# Sensor.net
KiCad netlist of a schematic drawn in Altium Designer
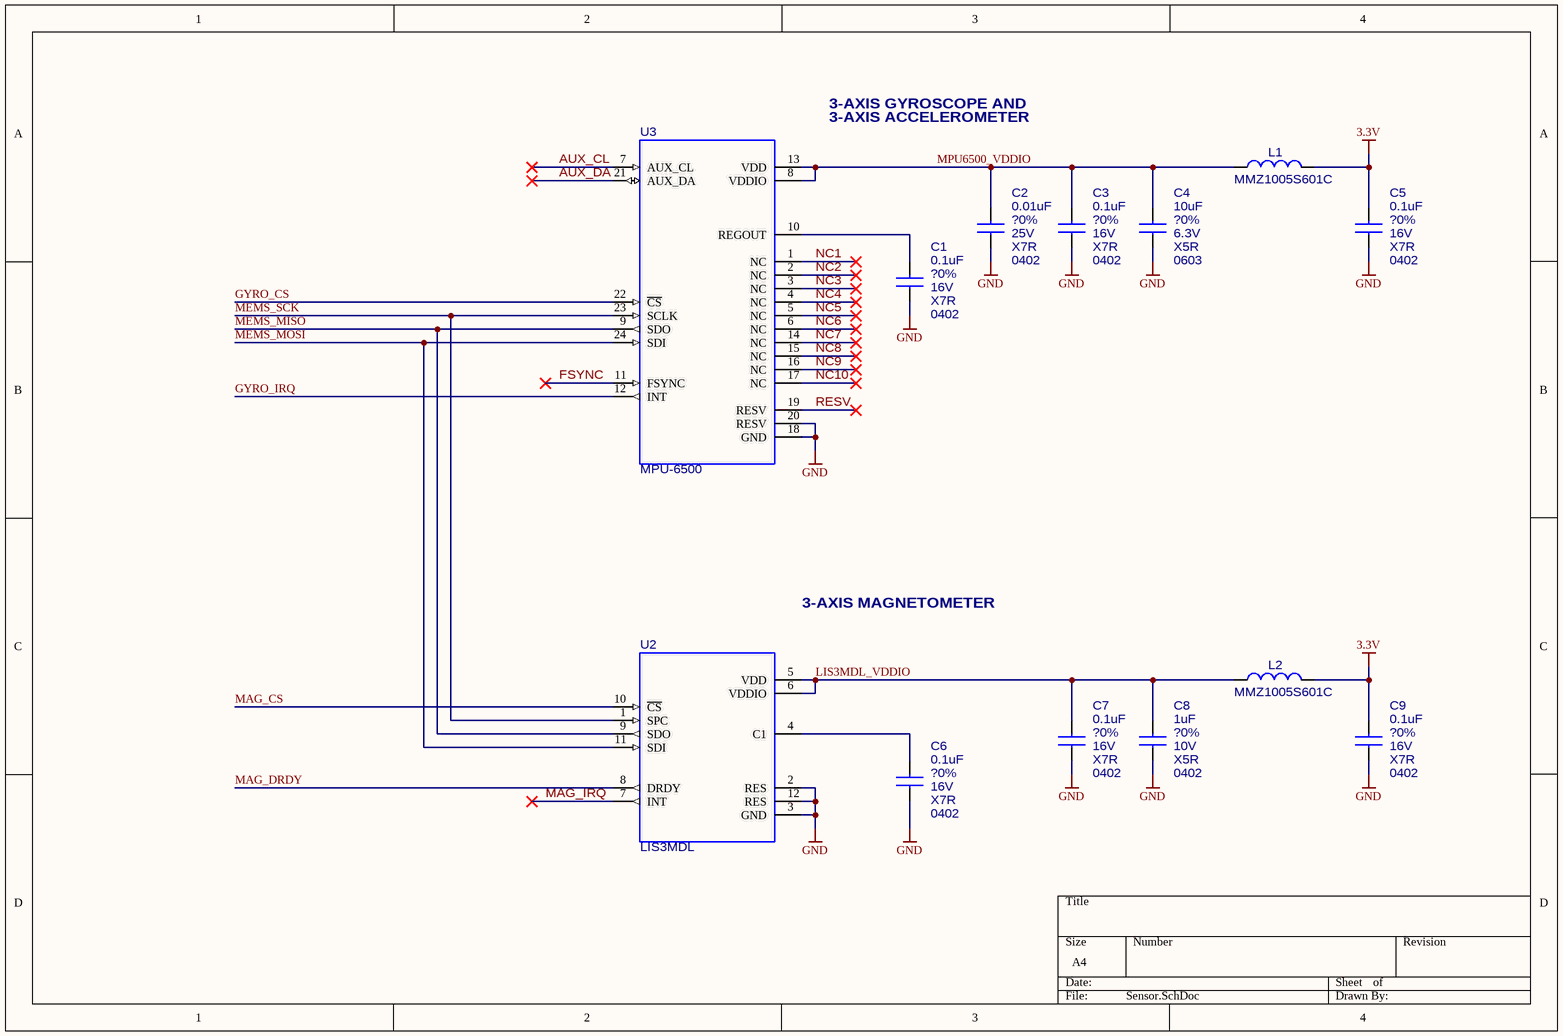
[diagram p0: Sensor.SchDoc]

(export (version "E")
  (design (tool "Eeschema 10.0.6"))
  (components
    (comp (ref "C1")
      (value "0.1uF")
      (footprint "CAP_CERAMIC_0402")
      (description "CAP, CERAMIC, 0.1uF, ?0%, 16V, X7R, 0402")
      (fields
        (field (name "MANUFACTURER") "MURATA ELECTRONICS")
        (field (name "PART NUMBER") "GRM155R71C104KA88D")
        (field (name "TOLERANCE") "?0%")
        (field (name "VOLTAGE") "16V")
        (field (name "DIELECTRIC") "X7R")
        (field (name "PACKAGE") "0402")
      )
      (libsource (lib "DK2") (part "CAP, CERAMIC"))
    )
    (comp (ref "C2")
      (value "0.01uF")
      (footprint "CAP_CERAMIC_0402")
      (description "CAP, CERAMIC, 0.01uF, ?0%, 25V, X7R, 0402")
      (fields
        (field (name "MANUFACTURER") "MURATA ELECTRONICS")
        (field (name "PART NUMBER") "GRM155R71E103KA01D")
        (field (name "TOLERANCE") "?0%")
        (field (name "VOLTAGE") "25V")
        (field (name "DIELECTRIC") "X7R")
        (field (name "PACKAGE") "0402")
      )
      (libsource (lib "DK2") (part "CAP, CERAMIC"))
    )
    (comp (ref "C3")
      (value "0.1uF")
      (footprint "CAP_CERAMIC_0402")
      (description "CAP, CERAMIC, 0.1uF, ?0%, 16V, X7R, 0402")
      (fields
        (field (name "MANUFACTURER") "MURATA ELECTRONICS")
        (field (name "PART NUMBER") "GRM155R71C104KA88D")
        (field (name "TOLERANCE") "?0%")
        (field (name "VOLTAGE") "16V")
        (field (name "DIELECTRIC") "X7R")
        (field (name "PACKAGE") "0402")
      )
      (libsource (lib "DK2") (part "CAP, CERAMIC"))
    )
    (comp (ref "C4")
      (value "10uF")
      (footprint "CAP_CERAMIC_0603")
      (description "CAP, CERAMIC, 10uF, ?0%, 6.3V, X5R, 0603")
      (fields
        (field (name "MANUFACTURER") "MURATA ELECTRONICS")
        (field (name "PART NUMBER") "GRM188R60J106ME47D")
        (field (name "TOLERANCE") "?0%")
        (field (name "VOLTAGE") "6.3V")
        (field (name "DIELECTRIC") "X5R")
        (field (name "PACKAGE") "0603")
      )
      (libsource (lib "DK2") (part "CAP, CERAMIC"))
    )
    (comp (ref "C5")
      (value "0.1uF")
      (footprint "CAP_CERAMIC_0402")
      (description "CAP, CERAMIC, 0.1uF, ?0%, 16V, X7R, 0402")
      (fields
        (field (name "MANUFACTURER") "MURATA ELECTRONICS")
        (field (name "PART NUMBER") "GRM155R71C104KA88D")
        (field (name "TOLERANCE") "?0%")
        (field (name "VOLTAGE") "16V")
        (field (name "DIELECTRIC") "X7R")
        (field (name "PACKAGE") "0402")
      )
      (libsource (lib "DK2") (part "CAP, CERAMIC"))
    )
    (comp (ref "C6")
      (value "0.1uF")
      (footprint "CAP_CERAMIC_0402")
      (description "CAP, CERAMIC, 0.1uF, ?0%, 16V, X7R, 0402")
      (fields
        (field (name "MANUFACTURER") "MURATA ELECTRONICS")
        (field (name "PART NUMBER") "GRM155R71C104KA88D")
        (field (name "TOLERANCE") "?0%")
        (field (name "VOLTAGE") "16V")
        (field (name "DIELECTRIC") "X7R")
        (field (name "PACKAGE") "0402")
      )
      (libsource (lib "DK2") (part "CAP, CERAMIC"))
    )
    (comp (ref "C7")
      (value "0.1uF")
      (footprint "CAP_CERAMIC_0402")
      (description "CAP, CERAMIC, 0.1uF, ?0%, 16V, X7R, 0402")
      (fields
        (field (name "MANUFACTURER") "MURATA ELECTRONICS")
        (field (name "PART NUMBER") "GRM155R71C104KA88D")
        (field (name "TOLERANCE") "?0%")
        (field (name "VOLTAGE") "16V")
        (field (name "DIELECTRIC") "X7R")
        (field (name "PACKAGE") "0402")
      )
      (libsource (lib "DK2") (part "CAP, CERAMIC"))
    )
    (comp (ref "C8")
      (value "1uF")
      (footprint "CAP_CERAMIC_0402")
      (description "CAP, CERAMIC, 1uF, ?0%, 10V, X5R, 0402")
      (fields
        (field (name "MANUFACTURER") "MURATA ELECTRONICS")
        (field (name "PART NUMBER") "GRM155R61A105KE15D")
        (field (name "TOLERANCE") "?0%")
        (field (name "VOLTAGE") "10V")
        (field (name "DIELECTRIC") "X5R")
        (field (name "PACKAGE") "0402")
      )
      (libsource (lib "DK2") (part "CAP, CERAMIC"))
    )
    (comp (ref "C9")
      (value "0.1uF")
      (footprint "CAP_CERAMIC_0402")
      (description "CAP, CERAMIC, 0.1uF, ?0%, 16V, X7R, 0402")
      (fields
        (field (name "MANUFACTURER") "MURATA ELECTRONICS")
        (field (name "PART NUMBER") "GRM155R71C104KA88D")
        (field (name "TOLERANCE") "?0%")
        (field (name "VOLTAGE") "16V")
        (field (name "DIELECTRIC") "X7R")
        (field (name "PACKAGE") "0402")
      )
      (libsource (lib "DK2") (part "CAP, CERAMIC"))
    )
    (comp (ref "L1")
      (value "MMZ1005S601C")
      (footprint "INDUCTOR_0402")
      (description "FERRITE CHIP BEAD, 600 OHM @ 100MHz, 300mA, 0402")
      (fields (field (name "MANUFACTURER") "TDK CORPORATION"))
      (libsource (lib "DK2") (part "INDUCTOR"))
    )
    (comp (ref "L2")
      (value "MMZ1005S601C")
      (footprint "INDUCTOR_0402")
      (description "FERRITE CHIP BEAD, 600 OHM @ 100MHz, 300mA, 0402")
      (fields (field (name "MANUFACTURER") "TDK CORPORATION"))
      (libsource (lib "DK2") (part "INDUCTOR"))
    )
    (comp (ref "U2")
      (value "LIS3MDL")
      (footprint "LGA-12")
      (description "IC, MEMS 3 AXIS MAGNETOMETER")
      (fields (field (name "MANUFACTURER") "STMICROELECTRONICS") (field (name "PART NUMBER") "LIS3MDLTR"))
      (libsource (lib "DK2") (part "LIS3MDL"))
    )
    (comp (ref "U3")
      (value "MPU-6500")
      (footprint "QFN-24")
      (description "IC, MEMS 3 AXIS GYROSCOPE AND 3 AXIS ACCELEROMETER")
      (fields (field (name "MANUFACTURER") "INVENSENSE"))
      (libsource (lib "DK2") (part "MPU-6500"))
    )
  )
  (nets
    (net (code "1") (name "/AUX_CL") (class "Default")
      (node (ref "U3") (pin "7") (pinfunction "AUX_CL_7") (pintype "input+no_connect"))
    )
    (net (code "2") (name "/AUX_DA") (class "Default")
      (node (ref "U3") (pin "21") (pinfunction "AUX_DA_21") (pintype "bidirectional+no_connect"))
    )
    (net (code "3") (name "/FSYNC") (class "Default")
      (node (ref "U3") (pin "11") (pinfunction "FSYNC_11") (pintype "input+no_connect"))
    )
    (net (code "4") (name "/GYRO_CS") (class "Default")
      (node (ref "U3") (pin "22") (pinfunction "~{CS}_22") (pintype "input"))
    )
    (net (code "5") (name "/GYRO_IRQ") (class "Default")
      (node (ref "U3") (pin "12") (pinfunction "INT_12") (pintype "output"))
    )
    (net (code "6") (name "/LIS3MDL_VDDIO") (class "Default")
      (node (ref "C7") (pin "1") (pinfunction "1_1") (pintype "passive"))
      (node (ref "C8") (pin "1") (pinfunction "1_1") (pintype "passive"))
      (node (ref "L2") (pin "1") (pinfunction "1_1") (pintype "passive"))
      (node (ref "U2") (pin "5") (pinfunction "VDD_5") (pintype "power_in"))
      (node (ref "U2") (pin "6") (pinfunction "VDDIO_6") (pintype "power_in"))
    )
    (net (code "7") (name "/MAG_CS") (class "Default")
      (node (ref "U2") (pin "10") (pinfunction "~{CS}_10") (pintype "input"))
    )
    (net (code "8") (name "/MAG_DRDY") (class "Default")
      (node (ref "U2") (pin "8") (pinfunction "DRDY_8") (pintype "output"))
    )
    (net (code "9") (name "/MAG_IRQ") (class "Default")
      (node (ref "U2") (pin "7") (pinfunction "INT_7") (pintype "output+no_connect"))
    )
    (net (code "10") (name "/MEMS_MISO") (class "Default")
      (node (ref "U2") (pin "9") (pinfunction "SDO_9") (pintype "output"))
      (node (ref "U3") (pin "9") (pinfunction "SDO_9") (pintype "output"))
    )
    (net (code "11") (name "/MEMS_MOSI") (class "Default")
      (node (ref "U2") (pin "11") (pinfunction "SDI_11") (pintype "input"))
      (node (ref "U3") (pin "24") (pinfunction "SDI_24") (pintype "input"))
    )
    (net (code "12") (name "/MEMS_SCK") (class "Default")
      (node (ref "U2") (pin "1") (pinfunction "SPC_1") (pintype "input"))
      (node (ref "U3") (pin "23") (pinfunction "SCLK_23") (pintype "input"))
    )
    (net (code "13") (name "/MPU6500_VDDIO") (class "Default")
      (node (ref "C2") (pin "1") (pinfunction "1_1") (pintype "passive"))
      (node (ref "C3") (pin "1") (pinfunction "1_1") (pintype "passive"))
      (node (ref "C4") (pin "1") (pinfunction "1_1") (pintype "passive"))
      (node (ref "L1") (pin "1") (pinfunction "1_1") (pintype "passive"))
      (node (ref "U3") (pin "13") (pinfunction "VDD_13") (pintype "power_in"))
      (node (ref "U3") (pin "8") (pinfunction "VDDIO_8") (pintype "power_in"))
    )
    (net (code "14") (name "/NC1") (class "Default")
      (node (ref "U3") (pin "1") (pinfunction "NC_1") (pintype "passive+no_connect"))
    )
    (net (code "15") (name "/NC2") (class "Default")
      (node (ref "U3") (pin "2") (pinfunction "NC_2") (pintype "passive+no_connect"))
    )
    (net (code "16") (name "/NC3") (class "Default")
      (node (ref "U3") (pin "3") (pinfunction "NC_3") (pintype "passive+no_connect"))
    )
    (net (code "17") (name "/NC4") (class "Default")
      (node (ref "U3") (pin "4") (pinfunction "NC_4") (pintype "passive+no_connect"))
    )
    (net (code "18") (name "/NC5") (class "Default")
      (node (ref "U3") (pin "5") (pinfunction "NC_5") (pintype "passive+no_connect"))
    )
    (net (code "19") (name "/NC6") (class "Default")
      (node (ref "U3") (pin "6") (pinfunction "NC_6") (pintype "passive+no_connect"))
    )
    (net (code "20") (name "/NC7") (class "Default")
      (node (ref "U3") (pin "14") (pinfunction "NC_14") (pintype "passive+no_connect"))
    )
    (net (code "21") (name "/NC8") (class "Default")
      (node (ref "U3") (pin "15") (pinfunction "NC_15") (pintype "passive+no_connect"))
    )
    (net (code "22") (name "/NC9") (class "Default")
      (node (ref "U3") (pin "16") (pinfunction "NC_16") (pintype "passive+no_connect"))
    )
    (net (code "23") (name "/NC10") (class "Default")
      (node (ref "U3") (pin "17") (pinfunction "NC_17") (pintype "passive+no_connect"))
    )
    (net (code "24") (name "/RESV") (class "Default")
      (node (ref "U3") (pin "19") (pinfunction "RESV_19") (pintype "passive+no_connect"))
    )
    (net (code "25") (name "3.3V") (class "Default")
      (node (ref "C5") (pin "1") (pinfunction "1_1") (pintype "passive"))
      (node (ref "C9") (pin "1") (pinfunction "1_1") (pintype "passive"))
      (node (ref "L1") (pin "2") (pinfunction "2_2") (pintype "passive"))
      (node (ref "L2") (pin "2") (pinfunction "2_2") (pintype "passive"))
    )
    (net (code "26") (name "GND") (class "Default")
      (node (ref "C1") (pin "2") (pinfunction "2_2") (pintype "passive"))
      (node (ref "C2") (pin "2") (pinfunction "2_2") (pintype "passive"))
      (node (ref "C3") (pin "2") (pinfunction "2_2") (pintype "passive"))
      (node (ref "C4") (pin "2") (pinfunction "2_2") (pintype "passive"))
      (node (ref "C5") (pin "2") (pinfunction "2_2") (pintype "passive"))
      (node (ref "C6") (pin "2") (pinfunction "2_2") (pintype "passive"))
      (node (ref "C7") (pin "2") (pinfunction "2_2") (pintype "passive"))
      (node (ref "C8") (pin "2") (pinfunction "2_2") (pintype "passive"))
      (node (ref "C9") (pin "2") (pinfunction "2_2") (pintype "passive"))
      (node (ref "U2") (pin "12") (pinfunction "RES_12") (pintype "passive"))
      (node (ref "U2") (pin "2") (pinfunction "RES_2") (pintype "passive"))
      (node (ref "U2") (pin "3") (pinfunction "GND_3") (pintype "power_in"))
      (node (ref "U3") (pin "18") (pinfunction "GND_18") (pintype "power_in"))
      (node (ref "U3") (pin "20") (pinfunction "RESV_20") (pintype "passive"))
    )
    (net (code "27") (name "Net-(U2-C1)") (class "Default")
      (node (ref "C6") (pin "1") (pinfunction "1_1") (pintype "passive"))
      (node (ref "U2") (pin "4") (pinfunction "C1_4") (pintype "passive"))
    )
    (net (code "28") (name "Net-(U3-REGOUT)") (class "Default")
      (node (ref "C1") (pin "1") (pinfunction "1_1") (pintype "passive"))
      (node (ref "U3") (pin "10") (pinfunction "REGOUT_10") (pintype "power_in"))
    )
  )
)
